# battery-addonnboard.net
KiCad netlist of a schematic drawn in EAGLE
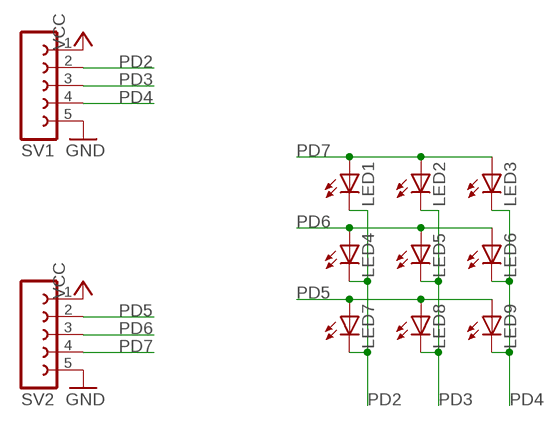
[diagram p0: schematic, sheet 1]

(export (version "E")
  (design (tool "Eeschema 10.0.6"))
  (components
    (comp (ref "LED1")
      (value "LED5MM")
      (footprint "eagle-import:LED5MM")
      (libsource (lib "eagle-import") (part "LED5MM"))
    )
    (comp (ref "LED2")
      (value "LED5MM")
      (footprint "eagle-import:LED5MM")
      (libsource (lib "eagle-import") (part "LED5MM"))
    )
    (comp (ref "LED3")
      (value "LED5MM")
      (footprint "eagle-import:LED5MM")
      (libsource (lib "eagle-import") (part "LED5MM"))
    )
    (comp (ref "LED4")
      (value "LED5MM")
      (footprint "eagle-import:LED5MM")
      (libsource (lib "eagle-import") (part "LED5MM"))
    )
    (comp (ref "LED5")
      (value "LED5MM")
      (footprint "eagle-import:LED5MM")
      (libsource (lib "eagle-import") (part "LED5MM"))
    )
    (comp (ref "LED6")
      (value "LED5MM")
      (footprint "eagle-import:LED5MM")
      (libsource (lib "eagle-import") (part "LED5MM"))
    )
    (comp (ref "LED7")
      (value "LED5MM")
      (footprint "eagle-import:LED5MM")
      (libsource (lib "eagle-import") (part "LED5MM"))
    )
    (comp (ref "LED8")
      (value "LED5MM")
      (footprint "eagle-import:LED5MM")
      (libsource (lib "eagle-import") (part "LED5MM"))
    )
    (comp (ref "LED9")
      (value "LED5MM")
      (footprint "eagle-import:LED5MM")
      (libsource (lib "eagle-import") (part "LED5MM"))
    )
    (comp (ref "SV1")
      (value "FE05-1")
      (footprint "eagle-import:FE05-1")
      (libsource (lib "eagle-import") (part "FE05-1"))
    )
    (comp (ref "SV2")
      (value "FE05-1")
      (footprint "eagle-import:FE05-1")
      (libsource (lib "eagle-import") (part "FE05-1"))
    )
  )
  (nets
    (net (code "1") (name "/PD2") (class "Default")
      (node (ref "LED1") (pin "K") (pinfunction "C_K") (pintype "passive"))
      (node (ref "LED4") (pin "K") (pinfunction "C_K") (pintype "passive"))
      (node (ref "LED7") (pin "K") (pinfunction "C_K") (pintype "passive"))
      (node (ref "SV1") (pin "2") (pinfunction "2_2") (pintype "passive"))
    )
    (net (code "2") (name "/PD3") (class "Default")
      (node (ref "LED2") (pin "K") (pinfunction "C_K") (pintype "passive"))
      (node (ref "LED5") (pin "K") (pinfunction "C_K") (pintype "passive"))
      (node (ref "LED8") (pin "K") (pinfunction "C_K") (pintype "passive"))
      (node (ref "SV1") (pin "3") (pinfunction "3_3") (pintype "passive"))
    )
    (net (code "3") (name "/PD4") (class "Default")
      (node (ref "LED3") (pin "K") (pinfunction "C_K") (pintype "passive"))
      (node (ref "LED6") (pin "K") (pinfunction "C_K") (pintype "passive"))
      (node (ref "LED9") (pin "K") (pinfunction "C_K") (pintype "passive"))
      (node (ref "SV1") (pin "4") (pinfunction "4_4") (pintype "passive"))
    )
    (net (code "4") (name "/PD5") (class "Default")
      (node (ref "LED7") (pin "A") (pinfunction "A_A") (pintype "passive"))
      (node (ref "LED8") (pin "A") (pinfunction "A_A") (pintype "passive"))
      (node (ref "LED9") (pin "A") (pinfunction "A_A") (pintype "passive"))
      (node (ref "SV2") (pin "2") (pinfunction "2_2") (pintype "passive"))
    )
    (net (code "5") (name "/PD6") (class "Default")
      (node (ref "LED4") (pin "A") (pinfunction "A_A") (pintype "passive"))
      (node (ref "LED5") (pin "A") (pinfunction "A_A") (pintype "passive"))
      (node (ref "LED6") (pin "A") (pinfunction "A_A") (pintype "passive"))
      (node (ref "SV2") (pin "3") (pinfunction "3_3") (pintype "passive"))
    )
    (net (code "6") (name "/PD7") (class "Default")
      (node (ref "LED1") (pin "A") (pinfunction "A_A") (pintype "passive"))
      (node (ref "LED2") (pin "A") (pinfunction "A_A") (pintype "passive"))
      (node (ref "LED3") (pin "A") (pinfunction "A_A") (pintype "passive"))
      (node (ref "SV2") (pin "4") (pinfunction "4_4") (pintype "passive"))
    )
    (net (code "7") (name "GND") (class "Default")
      (node (ref "SV1") (pin "5") (pinfunction "5_5") (pintype "passive"))
      (node (ref "SV2") (pin "5") (pinfunction "5_5") (pintype "passive"))
    )
    (net (code "8") (name "VCC") (class "Default")
      (node (ref "SV1") (pin "1") (pinfunction "1_1") (pintype "passive"))
      (node (ref "SV2") (pin "1") (pinfunction "1_1") (pintype "passive"))
    )
  )
)
